# 13_RESTOREFLAGS.net
KiCad netlist of a schematic drawn in EAGLE
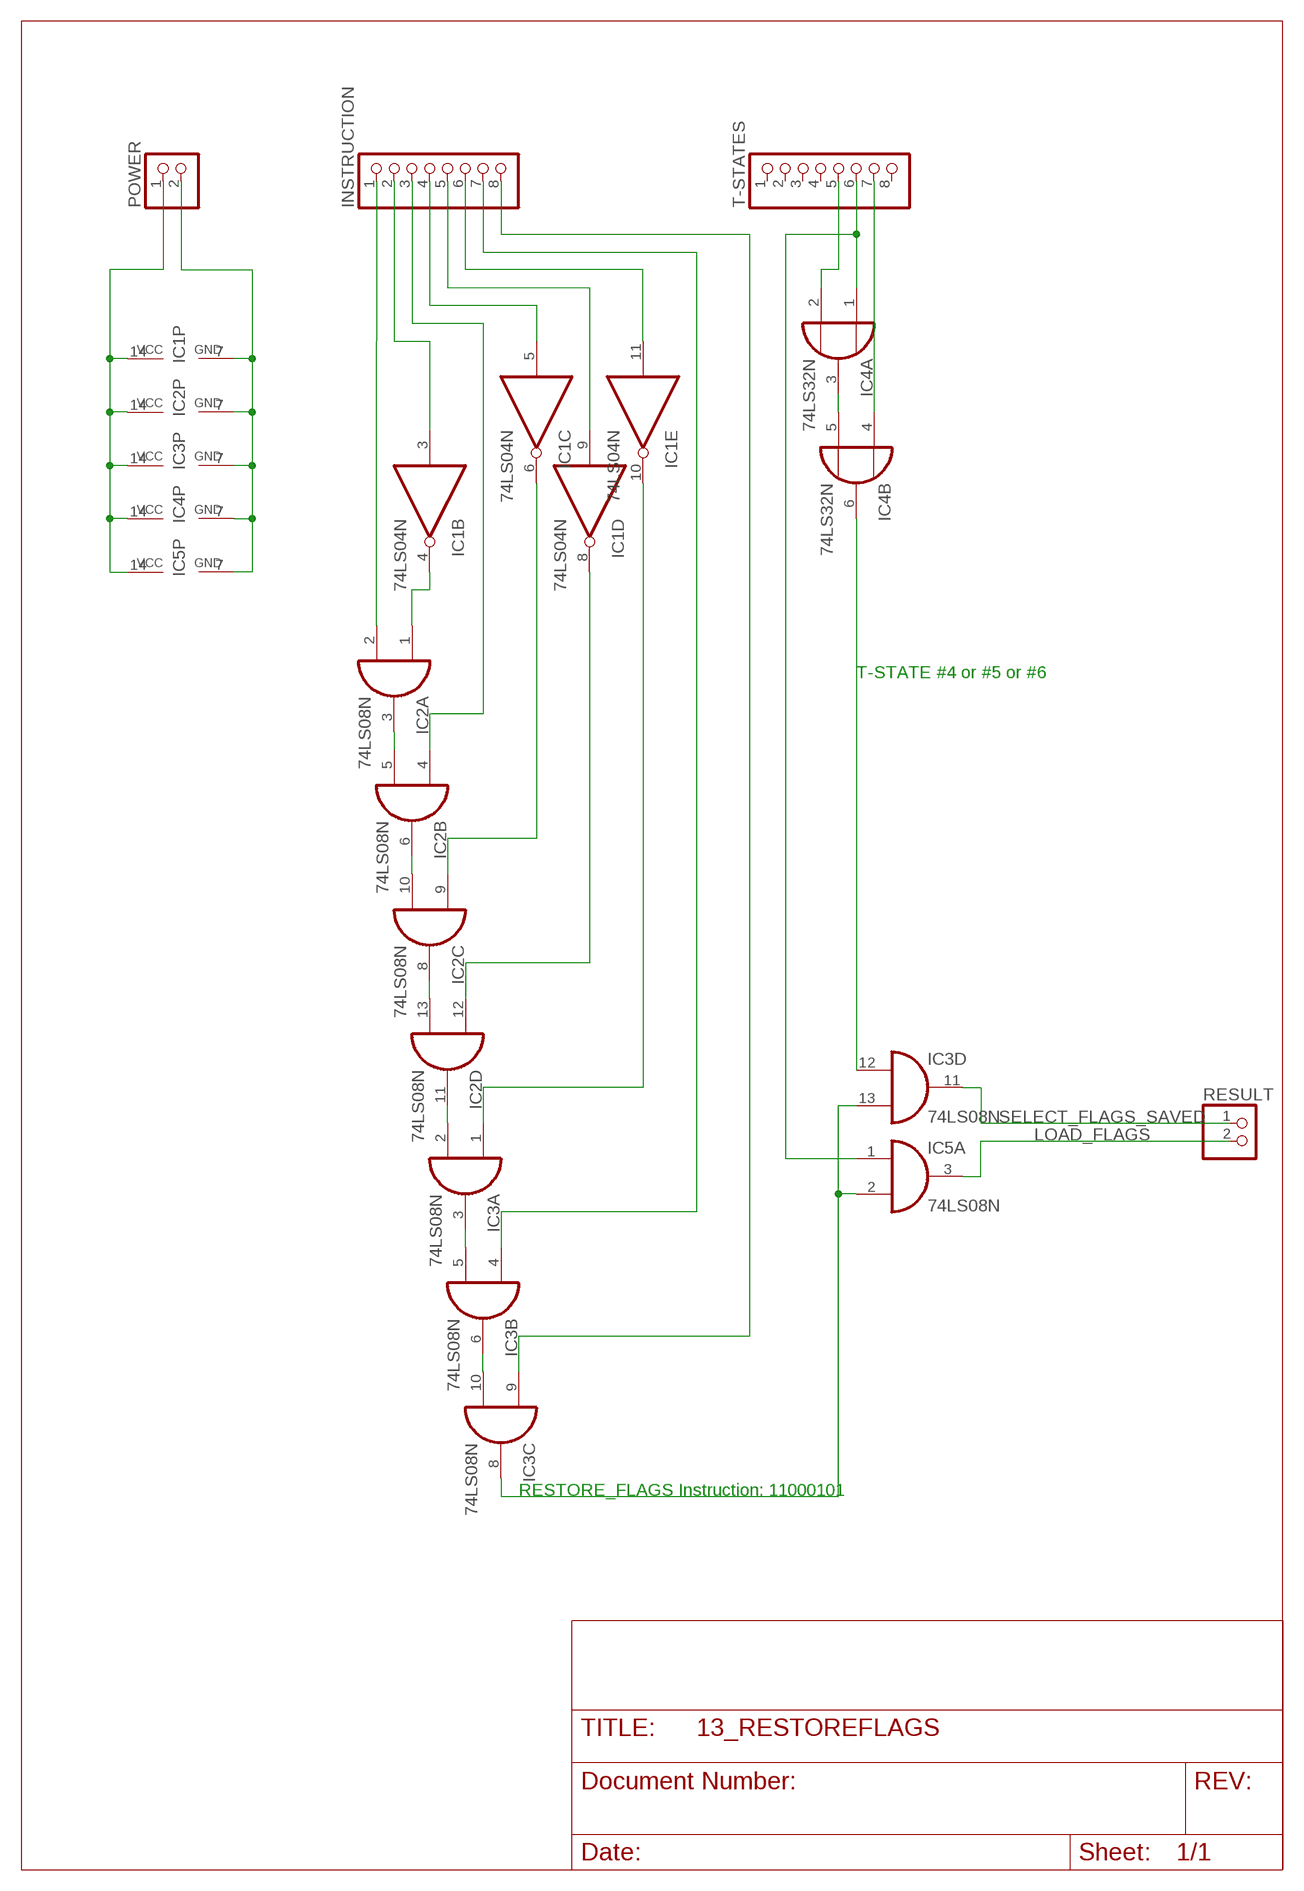
[diagram p0: schematic, sheet 1]

(export (version "E")
  (design (tool "Eeschema 10.0.6"))
  (components
    (comp (ref "IC1")
      (value "74LS04N")
      (footprint "eagle-import:DIL14")
      (libsource (lib "eagle-import") (part "7404NLS"))
    )
    (comp (ref "IC2")
      (value "74LS08N")
      (footprint "eagle-import:DIL14")
      (libsource (lib "eagle-import") (part "7408NLS"))
    )
    (comp (ref "IC3")
      (value "74LS08N")
      (footprint "eagle-import:DIL14")
      (libsource (lib "eagle-import") (part "7408NLS"))
    )
    (comp (ref "IC4")
      (value "74LS32N")
      (footprint "eagle-import:DIL14")
      (libsource (lib "eagle-import") (part "7432NLS"))
    )
    (comp (ref "IC5")
      (value "74LS08N")
      (footprint "eagle-import:DIL14")
      (libsource (lib "eagle-import") (part "7408NLS"))
    )
    (comp (ref "INSTRUCTION")
      (value "PINHD-1X8")
      (footprint "eagle-import:1X08")
      (libsource (lib "eagle-import") (part "PINHD-1X8"))
    )
    (comp (ref "POWER")
      (value "PINHD-1X2")
      (footprint "eagle-import:1X02")
      (libsource (lib "eagle-import") (part "PINHD-1X2"))
    )
    (comp (ref "RESULT")
      (value "PINHD-1X2")
      (footprint "eagle-import:1X02")
      (libsource (lib "eagle-import") (part "PINHD-1X2"))
    )
    (comp (ref "T-STATES")
      (value "PINHD-1X8")
      (footprint "eagle-import:1X08")
      (libsource (lib "eagle-import") (part "PINHD-1X8"))
    )
  )
  (nets
    (net (code "1") (name "/LOAD_FLAGS") (class "Default")
      (node (ref "IC5") (pin "3") (pinfunction "O_3") (pintype "output"))
      (node (ref "RESULT") (pin "2") (pinfunction "2_2") (pintype "passive"))
    )
    (net (code "2") (name "/SELECT_FLAGS_SAVED") (class "Default")
      (node (ref "IC3") (pin "11") (pinfunction "O_11") (pintype "output"))
      (node (ref "RESULT") (pin "1") (pinfunction "1_1") (pintype "passive"))
    )
    (net (code "3") (name "Net-(IC1B-I)") (class "Default")
      (node (ref "IC1") (pin "3") (pinfunction "I_3") (pintype "input"))
      (node (ref "INSTRUCTION") (pin "2") (pinfunction "2_2") (pintype "passive"))
    )
    (net (code "4") (name "Net-(IC1B-O)") (class "Default")
      (node (ref "IC1") (pin "4") (pinfunction "O_4") (pintype "output"))
      (node (ref "IC2") (pin "1") (pinfunction "I0_1") (pintype "input"))
    )
    (net (code "5") (name "Net-(IC1C-I)") (class "Default")
      (node (ref "IC1") (pin "5") (pinfunction "I_5") (pintype "input"))
      (node (ref "INSTRUCTION") (pin "4") (pinfunction "4_4") (pintype "passive"))
    )
    (net (code "6") (name "Net-(IC1C-O)") (class "Default")
      (node (ref "IC1") (pin "6") (pinfunction "O_6") (pintype "output"))
      (node (ref "IC2") (pin "9") (pinfunction "I0_9") (pintype "input"))
    )
    (net (code "7") (name "Net-(IC1D-I)") (class "Default")
      (node (ref "IC1") (pin "9") (pinfunction "I_9") (pintype "input"))
      (node (ref "INSTRUCTION") (pin "5") (pinfunction "5_5") (pintype "passive"))
    )
    (net (code "8") (name "Net-(IC1D-O)") (class "Default")
      (node (ref "IC1") (pin "8") (pinfunction "O_8") (pintype "output"))
      (node (ref "IC2") (pin "12") (pinfunction "I0_12") (pintype "input"))
    )
    (net (code "9") (name "Net-(IC1E-I)") (class "Default")
      (node (ref "IC1") (pin "11") (pinfunction "I_11") (pintype "input"))
      (node (ref "INSTRUCTION") (pin "6") (pinfunction "6_6") (pintype "passive"))
    )
    (net (code "10") (name "Net-(IC1E-O)") (class "Default")
      (node (ref "IC1") (pin "10") (pinfunction "O_10") (pintype "output"))
      (node (ref "IC3") (pin "1") (pinfunction "I0_1") (pintype "input"))
    )
    (net (code "11") (name "Net-(IC1G-GND)") (class "Default")
      (node (ref "IC1") (pin "7") (pinfunction "GND_7") (pintype "power_in"))
      (node (ref "IC2") (pin "7") (pinfunction "GND_7") (pintype "power_in"))
      (node (ref "IC3") (pin "7") (pinfunction "GND_7") (pintype "power_in"))
      (node (ref "IC4") (pin "7") (pinfunction "GND_7") (pintype "power_in"))
      (node (ref "IC5") (pin "7") (pinfunction "GND_7") (pintype "power_in"))
      (node (ref "POWER") (pin "2") (pinfunction "2_2") (pintype "passive"))
    )
    (net (code "12") (name "Net-(IC1G-VCC)") (class "Default")
      (node (ref "IC1") (pin "14") (pinfunction "VCC_14") (pintype "power_in"))
      (node (ref "IC2") (pin "14") (pinfunction "VCC_14") (pintype "power_in"))
      (node (ref "IC3") (pin "14") (pinfunction "VCC_14") (pintype "power_in"))
      (node (ref "IC4") (pin "14") (pinfunction "VCC_14") (pintype "power_in"))
      (node (ref "IC5") (pin "14") (pinfunction "VCC_14") (pintype "power_in"))
      (node (ref "POWER") (pin "1") (pinfunction "1_1") (pintype "passive"))
    )
    (net (code "13") (name "Net-(IC2A-I1)") (class "Default")
      (node (ref "IC2") (pin "2") (pinfunction "I1_2") (pintype "input"))
      (node (ref "INSTRUCTION") (pin "1") (pinfunction "1_1") (pintype "passive"))
    )
    (net (code "14") (name "Net-(IC2A-O)") (class "Default")
      (node (ref "IC2") (pin "3") (pinfunction "O_3") (pintype "output"))
      (node (ref "IC2") (pin "5") (pinfunction "I1_5") (pintype "input"))
    )
    (net (code "15") (name "Net-(IC2B-I0)") (class "Default")
      (node (ref "IC2") (pin "4") (pinfunction "I0_4") (pintype "input"))
      (node (ref "INSTRUCTION") (pin "3") (pinfunction "3_3") (pintype "passive"))
    )
    (net (code "16") (name "Net-(IC2B-O)") (class "Default")
      (node (ref "IC2") (pin "10") (pinfunction "I1_10") (pintype "input"))
      (node (ref "IC2") (pin "6") (pinfunction "O_6") (pintype "output"))
    )
    (net (code "17") (name "Net-(IC2C-O)") (class "Default")
      (node (ref "IC2") (pin "13") (pinfunction "I1_13") (pintype "input"))
      (node (ref "IC2") (pin "8") (pinfunction "O_8") (pintype "output"))
    )
    (net (code "18") (name "Net-(IC2D-O)") (class "Default")
      (node (ref "IC2") (pin "11") (pinfunction "O_11") (pintype "output"))
      (node (ref "IC3") (pin "2") (pinfunction "I1_2") (pintype "input"))
    )
    (net (code "19") (name "Net-(IC3A-O)") (class "Default")
      (node (ref "IC3") (pin "3") (pinfunction "O_3") (pintype "output"))
      (node (ref "IC3") (pin "5") (pinfunction "I1_5") (pintype "input"))
    )
    (net (code "20") (name "Net-(IC3B-I0)") (class "Default")
      (node (ref "IC3") (pin "4") (pinfunction "I0_4") (pintype "input"))
      (node (ref "INSTRUCTION") (pin "7") (pinfunction "7_7") (pintype "passive"))
    )
    (net (code "21") (name "Net-(IC3B-O)") (class "Default")
      (node (ref "IC3") (pin "10") (pinfunction "I1_10") (pintype "input"))
      (node (ref "IC3") (pin "6") (pinfunction "O_6") (pintype "output"))
    )
    (net (code "22") (name "Net-(IC3C-I0)") (class "Default")
      (node (ref "IC3") (pin "9") (pinfunction "I0_9") (pintype "input"))
      (node (ref "INSTRUCTION") (pin "8") (pinfunction "8_8") (pintype "passive"))
    )
    (net (code "23") (name "Net-(IC3C-O)") (class "Default")
      (node (ref "IC3") (pin "13") (pinfunction "I1_13") (pintype "input"))
      (node (ref "IC3") (pin "8") (pinfunction "O_8") (pintype "output"))
      (node (ref "IC5") (pin "2") (pinfunction "I1_2") (pintype "input"))
    )
    (net (code "24") (name "Net-(IC3D-I0)") (class "Default")
      (node (ref "IC3") (pin "12") (pinfunction "I0_12") (pintype "input"))
      (node (ref "IC4") (pin "6") (pinfunction "O_6") (pintype "output"))
    )
    (net (code "25") (name "Net-(IC4A-I0)") (class "Default")
      (node (ref "IC4") (pin "1") (pinfunction "I0_1") (pintype "input"))
      (node (ref "IC5") (pin "1") (pinfunction "I0_1") (pintype "input"))
      (node (ref "T-STATES") (pin "6") (pinfunction "6_6") (pintype "passive"))
    )
    (net (code "26") (name "Net-(IC4A-I1)") (class "Default")
      (node (ref "IC4") (pin "2") (pinfunction "I1_2") (pintype "input"))
      (node (ref "T-STATES") (pin "5") (pinfunction "5_5") (pintype "passive"))
    )
    (net (code "27") (name "Net-(IC4A-O)") (class "Default")
      (node (ref "IC4") (pin "3") (pinfunction "O_3") (pintype "output"))
      (node (ref "IC4") (pin "5") (pinfunction "I1_5") (pintype "input"))
    )
    (net (code "28") (name "Net-(IC4B-I0)") (class "Default")
      (node (ref "IC4") (pin "4") (pinfunction "I0_4") (pintype "input"))
      (node (ref "T-STATES") (pin "7") (pinfunction "7_7") (pintype "passive"))
    )
    (net (code "29") (name "unconnected-(T-STATES-Pad1)") (class "Default")
      (node (ref "T-STATES") (pin "1") (pinfunction "1_1") (pintype "passive"))
    )
    (net (code "30") (name "unconnected-(T-STATES-Pad2)") (class "Default")
      (node (ref "T-STATES") (pin "2") (pinfunction "2_2") (pintype "passive"))
    )
    (net (code "31") (name "unconnected-(T-STATES-Pad3)") (class "Default")
      (node (ref "T-STATES") (pin "3") (pinfunction "3_3") (pintype "passive"))
    )
    (net (code "32") (name "unconnected-(T-STATES-Pad4)") (class "Default")
      (node (ref "T-STATES") (pin "4") (pinfunction "4_4") (pintype "passive"))
    )
    (net (code "33") (name "unconnected-(T-STATES-Pad8)") (class "Default")
      (node (ref "T-STATES") (pin "8") (pinfunction "8_8") (pintype "passive"))
    )
  )
)
